# ME433_PCB.net
KiCad netlist of a schematic drawn in EAGLE
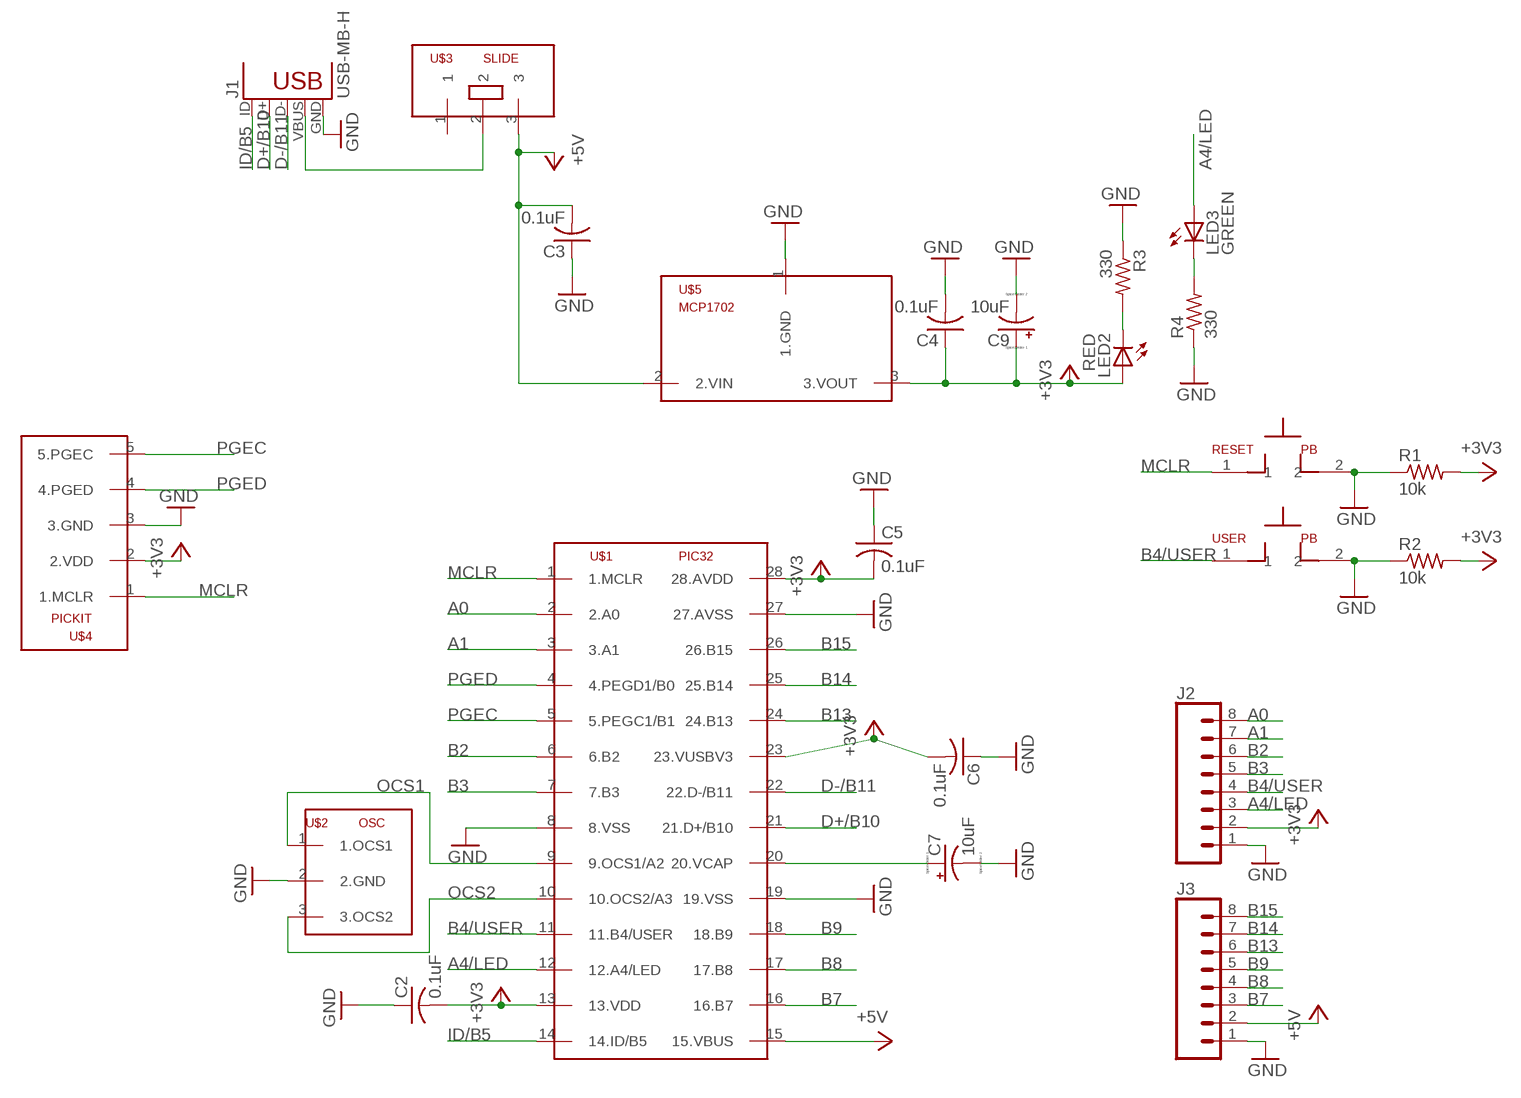
[diagram p0: schematic, sheet 1]

(export (version "E")
  (design (tool "Eeschema 10.0.6"))
  (components
    (comp (ref "C2")
      (value "0.1uF")
      (footprint "eagle-import:C025-025X050")
      (libsource (lib "eagle-import") (part "C-US025-025X050"))
    )
    (comp (ref "C3")
      (value "0.1uF")
      (footprint "eagle-import:C025-025X050")
      (libsource (lib "eagle-import") (part "C-US025-025X050"))
    )
    (comp (ref "C4")
      (value "0.1uF")
      (footprint "eagle-import:C025-025X050")
      (libsource (lib "eagle-import") (part "C-US025-025X050"))
    )
    (comp (ref "C5")
      (value "0.1uF")
      (footprint "eagle-import:C025-025X050")
      (libsource (lib "eagle-import") (part "C-US025-025X050"))
    )
    (comp (ref "C6")
      (value "0.1uF")
      (footprint "eagle-import:C025-025X050")
      (libsource (lib "eagle-import") (part "C-US025-025X050"))
    )
    (comp (ref "C7")
      (value "10uF")
      (footprint "eagle-import:B45181B")
      (libsource (lib "eagle-import") (part "CPOL-USB45181B"))
    )
    (comp (ref "C9")
      (value "10uF")
      (footprint "eagle-import:B45181B")
      (libsource (lib "eagle-import") (part "CPOL-USB45181B"))
    )
    (comp (ref "J1")
      (value "USB-MB-H")
      (footprint "eagle-import:USB-MB-H")
      (libsource (lib "eagle-import") (part "USB-MB-H"))
    )
    (comp (ref "J2")
      (value "CONN_08\"")
      (footprint "eagle-import:1X08")
      (libsource (lib "eagle-import") (part "CONN_08{dblquote}"))
    )
    (comp (ref "J3")
      (value "CONN_08\"")
      (footprint "eagle-import:1X08")
      (libsource (lib "eagle-import") (part "CONN_08{dblquote}"))
    )
    (comp (ref "LED2")
      (value "RED")
      (footprint "eagle-import:LED3MM")
      (libsource (lib "eagle-import") (part "LED3MM"))
    )
    (comp (ref "LED3")
      (value "GREEN")
      (footprint "eagle-import:LED3MM")
      (libsource (lib "eagle-import") (part "LED3MM"))
    )
    (comp (ref "R1")
      (value "10k")
      (footprint "eagle-import:0204_7")
      (libsource (lib "eagle-import") (part "R-US_0204/7"))
    )
    (comp (ref "R2")
      (value "10k")
      (footprint "eagle-import:0204_7")
      (libsource (lib "eagle-import") (part "R-US_0204/7"))
    )
    (comp (ref "R3")
      (value "330")
      (footprint "eagle-import:0204_7")
      (libsource (lib "eagle-import") (part "R-US_0204/7"))
    )
    (comp (ref "R4")
      (value "330")
      (footprint "eagle-import:0204_7")
      (libsource (lib "eagle-import") (part "R-US_0204/7"))
    )
    (comp (ref "RESET")
      (value "PB")
      (footprint "eagle-import:PB")
      (libsource (lib "eagle-import") (part "PB"))
    )
    (comp (ref "U$1")
      (value "PIC32")
      (footprint "eagle-import:DIL28-3")
      (libsource (lib "eagle-import") (part "PIC32"))
    )
    (comp (ref "U$2")
      (value "OSC")
      (footprint "eagle-import:OSC")
      (libsource (lib "eagle-import") (part "OSC"))
    )
    (comp (ref "U$3")
      (value "SLIDE")
      (footprint "eagle-import:SLIDE")
      (libsource (lib "eagle-import") (part "SLIDE"))
    )
    (comp (ref "U$4")
      (value "PICKIT")
      (footprint "eagle-import:1X05")
      (libsource (lib "eagle-import") (part "PICKIT"))
    )
    (comp (ref "U$5")
      (value "MCP1702")
      (footprint "eagle-import:TO92")
      (libsource (lib "eagle-import") (part "MCP1702"))
    )
    (comp (ref "USER")
      (value "PB")
      (footprint "eagle-import:PB")
      (libsource (lib "eagle-import") (part "PB"))
    )
  )
  (nets
    (net (code "1") (name "+3V3") (class "Default")
      (node (ref "C2") (pin "2") (pinfunction "2_2") (pintype "passive"))
      (node (ref "C4") (pin "1") (pinfunction "1_1") (pintype "passive"))
      (node (ref "C5") (pin "2") (pinfunction "2_2") (pintype "passive"))
      (node (ref "C6") (pin "2") (pinfunction "2_2") (pintype "passive"))
      (node (ref "C9") (pin "+") (pinfunction "+_+") (pintype "passive"))
      (node (ref "J2") (pin "2") (pinfunction "2_2") (pintype "passive"))
      (node (ref "LED2") (pin "A") (pinfunction "A_A") (pintype "passive"))
      (node (ref "R1") (pin "2") (pinfunction "2_2") (pintype "passive"))
      (node (ref "R2") (pin "2") (pinfunction "2_2") (pintype "passive"))
      (node (ref "U$1") (pin "13") (pinfunction "13.VDD_13") (pintype "bidirectional"))
      (node (ref "U$1") (pin "23") (pinfunction "23.VUSBV3_23") (pintype "bidirectional"))
      (node (ref "U$1") (pin "28") (pinfunction "28.AVDD_28") (pintype "bidirectional"))
      (node (ref "U$4") (pin "2") (pinfunction "2.VDD_2") (pintype "bidirectional"))
      (node (ref "U$5") (pin "3") (pinfunction "3.VOUT_3") (pintype "bidirectional"))
    )
    (net (code "2") (name "+5V") (class "Default")
      (node (ref "C3") (pin "2") (pinfunction "2_2") (pintype "passive"))
      (node (ref "J3") (pin "2") (pinfunction "2_2") (pintype "passive"))
      (node (ref "U$1") (pin "15") (pinfunction "15.VBUS_15") (pintype "bidirectional"))
      (node (ref "U$3") (pin "3") (pinfunction "3_3") (pintype "bidirectional"))
      (node (ref "U$5") (pin "2") (pinfunction "2.VIN_2") (pintype "bidirectional"))
    )
    (net (code "3") (name "/A0") (class "Default")
      (node (ref "J2") (pin "8") (pinfunction "8_8") (pintype "passive"))
      (node (ref "U$1") (pin "2") (pinfunction "2.A0_2") (pintype "bidirectional"))
    )
    (net (code "4") (name "/A1") (class "Default")
      (node (ref "J2") (pin "7") (pinfunction "7_7") (pintype "passive"))
      (node (ref "U$1") (pin "3") (pinfunction "3.A1_3") (pintype "bidirectional"))
    )
    (net (code "5") (name "/A4{slash}LED") (class "Default")
      (node (ref "J2") (pin "3") (pinfunction "3_3") (pintype "passive"))
      (node (ref "LED3") (pin "A") (pinfunction "A_A") (pintype "passive"))
      (node (ref "U$1") (pin "12") (pinfunction "12.A4/LED_12") (pintype "bidirectional"))
    )
    (net (code "6") (name "/B2") (class "Default")
      (node (ref "J2") (pin "6") (pinfunction "6_6") (pintype "passive"))
      (node (ref "U$1") (pin "6") (pinfunction "6.B2_6") (pintype "bidirectional"))
    )
    (net (code "7") (name "/B3") (class "Default")
      (node (ref "J2") (pin "5") (pinfunction "5_5") (pintype "passive"))
      (node (ref "U$1") (pin "7") (pinfunction "7.B3_7") (pintype "bidirectional"))
    )
    (net (code "8") (name "/B4{slash}USER") (class "Default")
      (node (ref "J2") (pin "4") (pinfunction "4_4") (pintype "passive"))
      (node (ref "U$1") (pin "11") (pinfunction "11.B4/USER_11") (pintype "bidirectional"))
      (node (ref "USER") (pin "1") (pinfunction "1_1") (pintype "bidirectional"))
    )
    (net (code "9") (name "/B7") (class "Default")
      (node (ref "J3") (pin "3") (pinfunction "3_3") (pintype "passive"))
      (node (ref "U$1") (pin "16") (pinfunction "16.B7_16") (pintype "bidirectional"))
    )
    (net (code "10") (name "/B8") (class "Default")
      (node (ref "J3") (pin "4") (pinfunction "4_4") (pintype "passive"))
      (node (ref "U$1") (pin "17") (pinfunction "17.B8_17") (pintype "bidirectional"))
    )
    (net (code "11") (name "/B9") (class "Default")
      (node (ref "J3") (pin "5") (pinfunction "5_5") (pintype "passive"))
      (node (ref "U$1") (pin "18") (pinfunction "18.B9_18") (pintype "bidirectional"))
    )
    (net (code "12") (name "/B13") (class "Default")
      (node (ref "J3") (pin "6") (pinfunction "6_6") (pintype "passive"))
      (node (ref "U$1") (pin "24") (pinfunction "24.B13_24") (pintype "bidirectional"))
    )
    (net (code "13") (name "/B14") (class "Default")
      (node (ref "J3") (pin "7") (pinfunction "7_7") (pintype "passive"))
      (node (ref "U$1") (pin "25") (pinfunction "25.B14_25") (pintype "bidirectional"))
    )
    (net (code "14") (name "/B15") (class "Default")
      (node (ref "J3") (pin "8") (pinfunction "8_8") (pintype "passive"))
      (node (ref "U$1") (pin "26") (pinfunction "26.B15_26") (pintype "bidirectional"))
    )
    (net (code "15") (name "/D+{slash}B10") (class "Default")
      (node (ref "J1") (pin "D+") (pinfunction "D+_D+") (pintype "bidirectional"))
      (node (ref "U$1") (pin "21") (pinfunction "21.D+/B10_21") (pintype "bidirectional"))
    )
    (net (code "16") (name "/D-{slash}B11") (class "Default")
      (node (ref "J1") (pin "D-") (pinfunction "D-_D-") (pintype "bidirectional"))
      (node (ref "U$1") (pin "22") (pinfunction "22.D-/B11_22") (pintype "bidirectional"))
    )
    (net (code "17") (name "/ID{slash}B5") (class "Default")
      (node (ref "J1") (pin "ID") (pinfunction "ID_ID") (pintype "bidirectional"))
      (node (ref "U$1") (pin "14") (pinfunction "14.ID/B5_14") (pintype "bidirectional"))
    )
    (net (code "18") (name "/MCLR") (class "Default")
      (node (ref "RESET") (pin "1") (pinfunction "1_1") (pintype "bidirectional"))
      (node (ref "U$1") (pin "1") (pinfunction "1.MCLR_1") (pintype "bidirectional"))
      (node (ref "U$4") (pin "1") (pinfunction "1.MCLR_1") (pintype "bidirectional"))
    )
    (net (code "19") (name "/OCS1") (class "Default")
      (node (ref "U$1") (pin "9") (pinfunction "9.OCS1/A2_9") (pintype "bidirectional"))
      (node (ref "U$2") (pin "1") (pinfunction "1.OCS1_1") (pintype "bidirectional"))
    )
    (net (code "20") (name "/OCS2") (class "Default")
      (node (ref "U$1") (pin "10") (pinfunction "10.OCS2/A3_10") (pintype "bidirectional"))
      (node (ref "U$2") (pin "3") (pinfunction "3.OCS2_3") (pintype "bidirectional"))
    )
    (net (code "21") (name "/PGEC") (class "Default")
      (node (ref "U$1") (pin "5") (pinfunction "5.PEGC1/B1_5") (pintype "bidirectional"))
      (node (ref "U$4") (pin "5") (pinfunction "5.PGEC_5") (pintype "bidirectional"))
    )
    (net (code "22") (name "/PGED") (class "Default")
      (node (ref "U$1") (pin "4") (pinfunction "4.PEGD1/B0_4") (pintype "bidirectional"))
      (node (ref "U$4") (pin "4") (pinfunction "4.PGED_4") (pintype "bidirectional"))
    )
    (net (code "23") (name "GND") (class "Default")
      (node (ref "C2") (pin "1") (pinfunction "1_1") (pintype "passive"))
      (node (ref "C3") (pin "1") (pinfunction "1_1") (pintype "passive"))
      (node (ref "C4") (pin "2") (pinfunction "2_2") (pintype "passive"))
      (node (ref "C5") (pin "1") (pinfunction "1_1") (pintype "passive"))
      (node (ref "C6") (pin "1") (pinfunction "1_1") (pintype "passive"))
      (node (ref "C7") (pin "-") (pinfunction "-_-") (pintype "passive"))
      (node (ref "C9") (pin "-") (pinfunction "-_-") (pintype "passive"))
      (node (ref "J1") (pin "GND") (pinfunction "GND_GND") (pintype "bidirectional"))
      (node (ref "J2") (pin "1") (pinfunction "1_1") (pintype "passive"))
      (node (ref "J3") (pin "1") (pinfunction "1_1") (pintype "passive"))
      (node (ref "R1") (pin "1") (pinfunction "1_1") (pintype "passive"))
      (node (ref "R2") (pin "1") (pinfunction "1_1") (pintype "passive"))
      (node (ref "R3") (pin "1") (pinfunction "1_1") (pintype "passive"))
      (node (ref "R4") (pin "1") (pinfunction "1_1") (pintype "passive"))
      (node (ref "RESET") (pin "2") (pinfunction "2_2") (pintype "bidirectional"))
      (node (ref "U$1") (pin "19") (pinfunction "19.VSS_19") (pintype "bidirectional"))
      (node (ref "U$1") (pin "27") (pinfunction "27.AVSS_27") (pintype "bidirectional"))
      (node (ref "U$1") (pin "8") (pinfunction "8.VSS_8") (pintype "bidirectional"))
      (node (ref "U$2") (pin "2") (pinfunction "2.GND_2") (pintype "bidirectional"))
      (node (ref "U$4") (pin "3") (pinfunction "3.GND_3") (pintype "bidirectional"))
      (node (ref "U$5") (pin "1") (pinfunction "1.GND_1") (pintype "bidirectional"))
      (node (ref "USER") (pin "2") (pinfunction "2_2") (pintype "bidirectional"))
    )
    (net (code "24") (name "Net-(J1-PadVBUS)") (class "Default")
      (node (ref "J1") (pin "VBUS") (pinfunction "VBUS_VBUS") (pintype "bidirectional"))
      (node (ref "U$3") (pin "2") (pinfunction "2_2") (pintype "bidirectional"))
    )
    (net (code "25") (name "Net-(LED2-C)") (class "Default")
      (node (ref "LED2") (pin "K") (pinfunction "C_K") (pintype "passive"))
      (node (ref "R3") (pin "2") (pinfunction "2_2") (pintype "passive"))
    )
    (net (code "26") (name "Net-(LED3-C)") (class "Default")
      (node (ref "LED3") (pin "K") (pinfunction "C_K") (pintype "passive"))
      (node (ref "R4") (pin "2") (pinfunction "2_2") (pintype "passive"))
    )
    (net (code "27") (name "Net-(U$1-20.VCAP)") (class "Default")
      (node (ref "C7") (pin "+") (pinfunction "+_+") (pintype "passive"))
      (node (ref "U$1") (pin "20") (pinfunction "20.VCAP_20") (pintype "bidirectional"))
    )
    (net (code "28") (name "unconnected-(U$3-Pad1)") (class "Default")
      (node (ref "U$3") (pin "1") (pinfunction "1_1") (pintype "bidirectional"))
    )
  )
)
